# ENC28J60EthernetInterface.net
KiCad netlist of a schematic drawn in Altium Designer
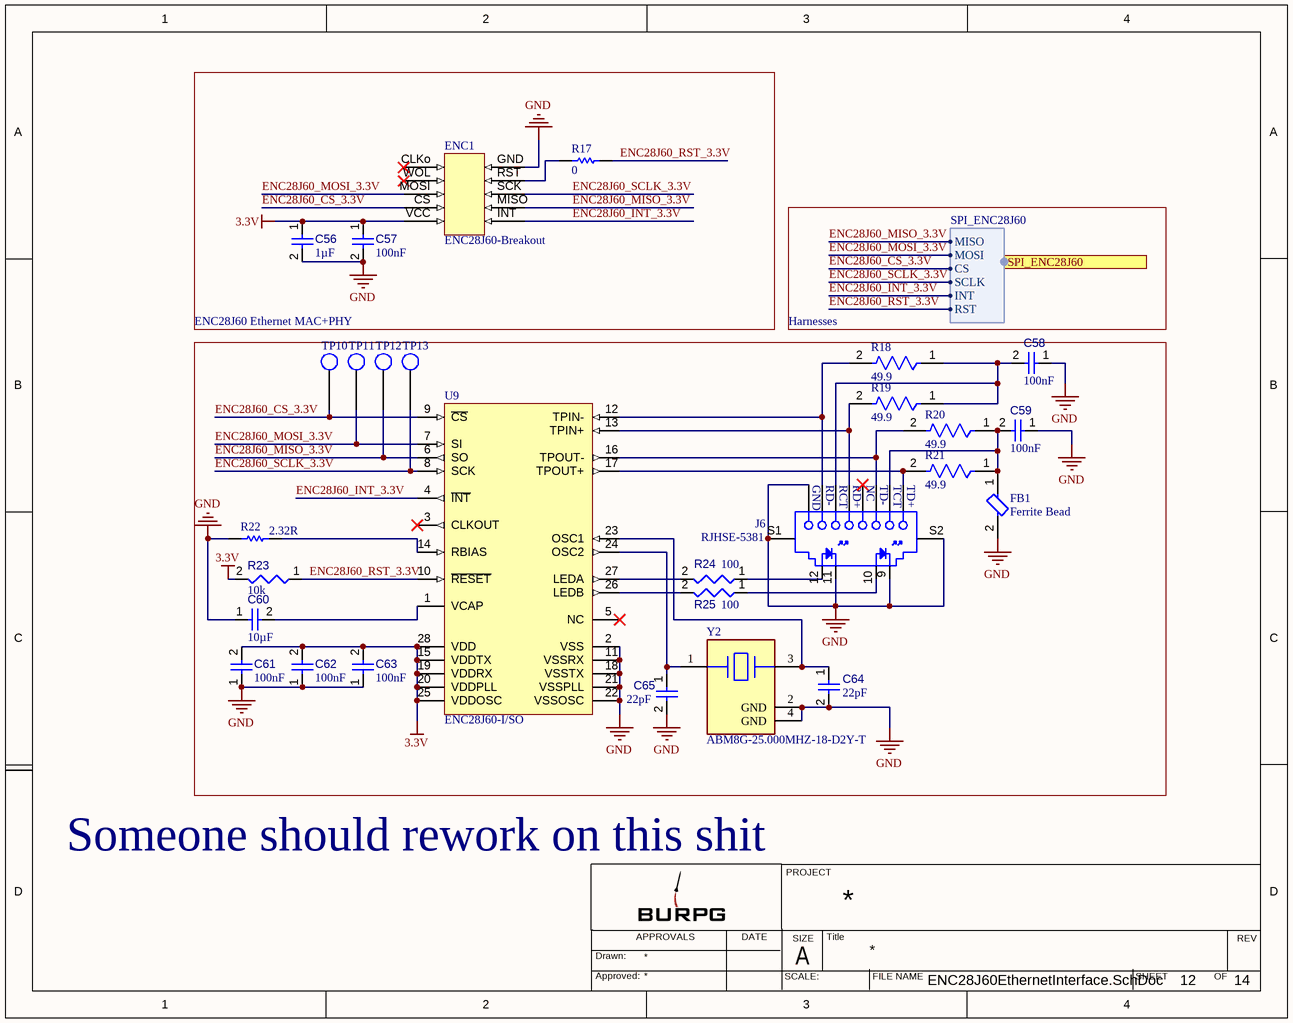
[diagram p0: ENC28J60EthernetInterface.SchDoc]

(export (version "E")
  (design (tool "Eeschema 10.0.6"))
  (components
    (comp (ref "C56")
      (value "1µF")
      (footprint "CAPC2013X135X45NL10T25")
      (description "Chip Capacitor, 1 uF, +/- 10%, 50 V, 0805 (2012 Metric)")
      (fields (field (name "TOLERANCE") "10%") (field (name "Comment") "Capacitor 1 uF +/- 10% 50 V 0805"))
      (libsource (lib "Boston University") (part "CAP-NP-2"))
    )
    (comp (ref "C57")
      (value "100nF")
      (footprint "CAPC2013X95X50LL10T25")
      (description "Chip Capacitor, 100 nF, +/- 10%, 50 V, 0805 (2012 Metric)")
      (fields (field (name "TOLERANCE") "10%") (field (name "Comment") "Capacitor 100 nF +/-10% 50 V 0805"))
      (libsource (lib "Boston University") (part "CAP-NP-2"))
    )
    (comp (ref "C58")
      (value "100nF")
      (footprint "CAPC1608X90X40NL10T20")
      (description "Chip Capacitor, 100 nF, +/- 10%, 50 V, 0603 (1608 Metric)")
      (fields (field (name "TOLERANCE") "10%") (field (name "Comment") "Capacitor 100 nF +/-10% 50 V 0603"))
      (libsource (lib "Boston University") (part "CAP-NP-2"))
    )
    (comp (ref "C59")
      (value "100nF")
      (footprint "CAPC1608X90X40NL10T20")
      (description "Chip Capacitor, 100 nF, +/- 10%, 50 V, 0603 (1608 Metric)")
      (fields (field (name "TOLERANCE") "10%") (field (name "Comment") "Capacitor 100 nF +/-10% 50 V 0603"))
      (libsource (lib "Boston University") (part "CAP-NP-2"))
    )
    (comp (ref "C60")
      (value "10µF")
      (footprint "CAPC0603(1608)100_L")
      (description "Chip Capacitor, 10µF +/-20%, 10V, 0603, Thickness 1 mm")
      (fields (field (name "TOLERANCE") "10%") (field (name "Comment") "Capacitor 10µF +/-20% 10V 0603"))
      (libsource (lib "Boston University") (part "CAP-NP-2"))
    )
    (comp (ref "C61")
      (value "100nF")
      (footprint "CAPC1608X90X40NL10T20")
      (description "Chip Capacitor, 100 nF, +/- 10%, 50 V, 0603 (1608 Metric)")
      (fields (field (name "TOLERANCE") "10%") (field (name "Comment") "Capacitor 100 nF +/-10% 50 V 0603"))
      (libsource (lib "Boston University") (part "CAP-NP-2"))
    )
    (comp (ref "C62")
      (value "100nF")
      (footprint "CAPC1608X90X40NL10T20")
      (description "Chip Capacitor, 100 nF, +/- 10%, 50 V, 0603 (1608 Metric)")
      (fields (field (name "TOLERANCE") "10%") (field (name "Comment") "Capacitor 100 nF +/-10% 50 V 0603"))
      (libsource (lib "Boston University") (part "CAP-NP-2"))
    )
    (comp (ref "C63")
      (value "100nF")
      (footprint "CAPC1608X90X40NL10T20")
      (description "Chip Capacitor, 100 nF, +/- 10%, 50 V, 0603 (1608 Metric)")
      (fields (field (name "TOLERANCE") "10%") (field (name "Comment") "Capacitor 100 nF +/-10% 50 V 0603"))
      (libsource (lib "Boston University") (part "CAP-NP-2"))
    )
    (comp (ref "C64")
      (value "22pF")
      (footprint "CAPC0402(1005)60_L")
      (description "Chip Capacitor, 22pF +/-10%, 50V, 0402, Thickness 0.6 mm")
      (fields (field (name "TOLERANCE") "10%") (field (name "Comment") "Capacitor 22pF +/-10% 50V 0402"))
      (libsource (lib "Boston University") (part "CAP-NP-2"))
    )
    (comp (ref "C65")
      (value "22pF")
      (footprint "CAPC0402(1005)60_L")
      (description "Chip Capacitor, 22pF +/-10%, 50V, 0402, Thickness 0.6 mm")
      (fields (field (name "TOLERANCE") "10%") (field (name "Comment") "Capacitor 22pF +/-10% 50V 0402"))
      (libsource (lib "Boston University") (part "CAP-NP-2"))
    )
    (comp (ref "ENC1")
      (value "ENC28J60-Breakout")
      (footprint "New footprint 1")
      (libsource (lib "Boston University") (part "New symbol 1"))
    )
    (comp (ref "FB1")
      (value "Ferrite Bead")
      (footprint "FP-MMZ1608-0_8-IPC_A")
      (description "Signal Line Ferrite Bead 60Ω  @ 100MHz 500mA DCR 150mΩ SMD 0603")
      (fields (field (name "TOLERANCE") "25%"))
      (libsource (lib "Altium Content Vault") (part "5f30dd21d616792df468990f7003faa"))
    )
    (comp (ref "J6")
      (value "RJHSE-5381")
      (footprint "AMPH-RJHSE-5381_V")
      (fields (field (name "MANUFACTURER") "Amphenol"))
      (libsource (lib "Altium Content Vault") (part "RJ45-12-2SHLD"))
    )
    (comp (ref "R17")
      (value "0")
      (footprint "RESC3216X60X45ML15T20")
      (description "Chip Resistor, 0 Ohm, +/- 5%, 0.25 W, -55 to 155 degC, 1206 (3216 Metric)")
      (fields (field (name "TOLERANCE") "5%") (field (name "POWER") "250mW"))
      (libsource (lib "Boston University") (part "RES-2"))
    )
    (comp (ref "R18")
      (value "49.9")
      (footprint "FP-ERJ6EN-MFG")
      (description "RES SMD 49.9 OHM 1% 1/8W 0805")
      (fields (field (name "TOLERANCE") "1%"))
      (libsource (lib "Altium Content Vault") (part "1029c3af85768c4190bb7ad29bc67b5"))
    )
    (comp (ref "R19")
      (value "49.9")
      (footprint "FP-ERJ6EN-MFG")
      (description "RES SMD 49.9 OHM 1% 1/8W 0805")
      (fields (field (name "TOLERANCE") "1%"))
      (libsource (lib "Altium Content Vault") (part "1029c3af85768c4190bb7ad29bc67b5"))
    )
    (comp (ref "R20")
      (value "49.9")
      (footprint "FP-ERJ6EN-MFG")
      (description "RES SMD 49.9 OHM 1% 1/8W 0805")
      (fields (field (name "TOLERANCE") "1%"))
      (libsource (lib "Altium Content Vault") (part "1029c3af85768c4190bb7ad29bc67b5"))
    )
    (comp (ref "R21")
      (value "49.9")
      (footprint "FP-ERJ6EN-MFG")
      (description "RES SMD 49.9 OHM 1% 1/8W 0805")
      (fields (field (name "TOLERANCE") "1%"))
      (libsource (lib "Altium Content Vault") (part "1029c3af85768c4190bb7ad29bc67b5"))
    )
    (comp (ref "R22")
      (value "2.32R")
      (footprint "RESC2013X70X40NL20T20")
      (fields (field (name "MANUFACTURER") "Panasonic") (field (name "PART NUMBER") "ERJ-6ENF2321V"))
      (libsource (lib "Altium Content Vault") (part "RES"))
    )
    (comp (ref "R23")
      (value "10k")
      (footprint "RESC1005X40X25ML05T05")
      (description "Chip Resistor, 10 KOhm, +/- 1%, 0.1 W, -55 to 155 degC, 0402 (1005 Metric)")
      (fields (field (name "POWER") "100mW") (field (name "TOLERANCE") "1%"))
      (libsource (lib "") (part "RES-2_1"))
    )
    (comp (ref "R24")
      (value "100")
      (footprint "RESC0402(1005)_L")
      (description "100R 0.063W 1% 0402 (1005 Metric)  SMD")
      (fields (field (name "POWER") "63mW") (field (name "TOLERANCE") "1%"))
      (libsource (lib "Boston University") (part "100R2F"))
    )
    (comp (ref "R25")
      (value "100")
      (footprint "RESC0402(1005)_L")
      (description "100R 0.063W 1% 0402 (1005 Metric)  SMD")
      (fields (field (name "POWER") "63mW") (field (name "TOLERANCE") "1%"))
      (libsource (lib "Boston University") (part "100R2F"))
    )
    (comp (ref "TP10")
      (value "BURPG_TestPoint1")
      (footprint "BURPG_TestPoint1")
      (libsource (lib "BURPG_generic") (part "BURPG_TestPoint1"))
    )
    (comp (ref "TP11")
      (value "BURPG_TestPoint1")
      (footprint "BURPG_TestPoint1")
      (libsource (lib "BURPG_generic") (part "BURPG_TestPoint1"))
    )
    (comp (ref "TP12")
      (value "BURPG_TestPoint1")
      (footprint "BURPG_TestPoint1")
      (libsource (lib "BURPG_generic") (part "BURPG_TestPoint1"))
    )
    (comp (ref "TP13")
      (value "BURPG_TestPoint1")
      (footprint "BURPG_TestPoint1")
      (libsource (lib "BURPG_generic") (part "BURPG_TestPoint1"))
    )
    (comp (ref "U9")
      (value "ENC28J60-I/SO")
      (footprint "SOIC-SO28_M")
      (description "Stand-Alone Ethernet Controller with SPI Interface, 28-Pin SOIC, Industrial Temperature")
      (libsource (lib "Altium Content Vault") (part "COM-ENET-ENC28J60-28"))
    )
    (comp (ref "Y2")
      (value "ABM8G-25.000MHZ-18-D2Y-T")
      (footprint "FP-ABM8G-MFG")
      (description "Crystal 25MHz ±20ppm (Tol) ±30ppm (Stability) 18pF FUND 60Ω 4-Pin SMD T/R")
      (fields (field (name "TOLERANCE") "20ppm"))
      (libsource (lib "Altium Content Vault") (part "48e526d86b7f2615d98721063c72f49"))
    )
  )
  (nets
    (net (code "2") (name "/ENC28J60_CS_3.3V") (class "Default")
      (node (ref "ENC1") (pin "CS") (pintype "input"))
      (node (ref "TP10") (pin "1") (pinfunction "1_1") (pintype "passive"))
      (node (ref "U9") (pin "9") (pinfunction "~{CS}_9") (pintype "input"))
    )
    (net (code "3") (name "/ENC28J60_INT_3.3V") (class "Default")
      (node (ref "ENC1") (pin "INT") (pintype "input"))
      (node (ref "U9") (pin "4") (pinfunction "~{INT}_4") (pintype "output"))
    )
    (net (code "4") (name "/ENC28J60_MISO_3.3V") (class "Default")
      (node (ref "ENC1") (pin "MISO") (pintype "input"))
      (node (ref "TP12") (pin "1") (pinfunction "1_1") (pintype "passive"))
      (node (ref "U9") (pin "6") (pinfunction "SO_6") (pintype "output"))
    )
    (net (code "5") (name "/ENC28J60_MOSI_3.3V") (class "Default")
      (node (ref "ENC1") (pin "MOSI") (pintype "input"))
      (node (ref "TP11") (pin "1") (pinfunction "1_1") (pintype "passive"))
      (node (ref "U9") (pin "7") (pinfunction "SI_7") (pintype "input"))
    )
    (net (code "6") (name "/ENC28J60_RST_3.3V") (class "Default")
      (node (ref "R17") (pin "2") (pinfunction "2_2") (pintype "passive"))
      (node (ref "R23") (pin "1") (pinfunction "1_1") (pintype "passive"))
      (node (ref "U9") (pin "10") (pinfunction "~{RESET}_10") (pintype "input"))
    )
    (net (code "7") (name "/ENC28J60_SCLK_3.3V") (class "Default")
      (node (ref "ENC1") (pin "SCK") (pintype "input"))
      (node (ref "TP13") (pin "1") (pinfunction "1_1") (pintype "passive"))
      (node (ref "U9") (pin "8") (pinfunction "SCK_8") (pintype "input"))
    )
    (net (code "9") (name "3.3V") (class "Default")
      (node (ref "C56") (pin "1") (pinfunction "1_1") (pintype "passive"))
      (node (ref "C57") (pin "1") (pinfunction "1_1") (pintype "passive"))
      (node (ref "C61") (pin "2") (pinfunction "2_2") (pintype "passive"))
      (node (ref "C62") (pin "2") (pinfunction "2_2") (pintype "passive"))
      (node (ref "C63") (pin "2") (pinfunction "2_2") (pintype "passive"))
      (node (ref "ENC1") (pin "VCC") (pintype "input"))
      (node (ref "R23") (pin "2") (pinfunction "2_2") (pintype "passive"))
      (node (ref "U9") (pin "15") (pinfunction "VDDTX_15") (pintype "power_in"))
      (node (ref "U9") (pin "19") (pinfunction "VDDRX_19") (pintype "power_in"))
      (node (ref "U9") (pin "20") (pinfunction "VDDPLL_20") (pintype "power_in"))
      (node (ref "U9") (pin "25") (pinfunction "VDDOSC_25") (pintype "power_in"))
      (node (ref "U9") (pin "28") (pinfunction "VDD_28") (pintype "power_in"))
    )
    (net (code "10") (name "GND") (class "Default")
      (node (ref "C56") (pin "2") (pinfunction "2_2") (pintype "passive"))
      (node (ref "C57") (pin "2") (pinfunction "2_2") (pintype "passive"))
      (node (ref "C58") (pin "1") (pinfunction "1_1") (pintype "passive"))
      (node (ref "C59") (pin "1") (pinfunction "1_1") (pintype "passive"))
      (node (ref "C60") (pin "1") (pinfunction "1_1") (pintype "passive"))
      (node (ref "C61") (pin "1") (pinfunction "1_1") (pintype "passive"))
      (node (ref "C62") (pin "1") (pinfunction "1_1") (pintype "passive"))
      (node (ref "C63") (pin "1") (pinfunction "1_1") (pintype "passive"))
      (node (ref "C64") (pin "2") (pinfunction "2_2") (pintype "passive"))
      (node (ref "C65") (pin "2") (pinfunction "2_2") (pintype "passive"))
      (node (ref "ENC1") (pin "GND") (pintype "input"))
      (node (ref "FB1") (pin "2") (pinfunction "2_2") (pintype "passive"))
      (node (ref "J6") (pin "11") (pinfunction "11_11") (pintype "passive"))
      (node (ref "J6") (pin "8") (pinfunction "GND_8") (pintype "passive"))
      (node (ref "J6") (pin "9") (pinfunction "9_9") (pintype "passive"))
      (node (ref "J6") (pin "S1") (pinfunction "S1_S1") (pintype "passive"))
      (node (ref "J6") (pin "S2") (pinfunction "S2_S2") (pintype "passive"))
      (node (ref "R22") (pin "1") (pinfunction "1_1") (pintype "passive"))
      (node (ref "U9") (pin "11") (pinfunction "VSSRX_11") (pintype "power_in"))
      (node (ref "U9") (pin "18") (pinfunction "VSSTX_18") (pintype "power_in"))
      (node (ref "U9") (pin "2") (pinfunction "VSS_2") (pintype "power_in"))
      (node (ref "U9") (pin "21") (pinfunction "VSSPLL_21") (pintype "power_in"))
      (node (ref "U9") (pin "22") (pinfunction "VSSOSC_22") (pintype "power_in"))
      (node (ref "Y2") (pin "2") (pinfunction "GND_2") (pintype "power_in"))
      (node (ref "Y2") (pin "4") (pinfunction "GND_4") (pintype "power_in"))
    )
    (net (code "11") (name "Net-(ENC1-PadRST)") (class "Default")
      (node (ref "ENC1") (pin "RST") (pintype "input"))
      (node (ref "R17") (pin "1") (pinfunction "1_1") (pintype "passive"))
    )
    (net (code "12") (name "Net-(J6-Pad10)") (class "Default")
      (node (ref "J6") (pin "10") (pinfunction "10_10") (pintype "passive"))
      (node (ref "R25") (pin "1") (pinfunction "1_1") (pintype "passive"))
    )
    (net (code "13") (name "Net-(J6-Pad12)") (class "Default")
      (node (ref "J6") (pin "12") (pinfunction "12_12") (pintype "passive"))
      (node (ref "R24") (pin "1") (pinfunction "1_1") (pintype "passive"))
    )
    (net (code "14") (name "Net-(J6-RCT)") (class "Default")
      (node (ref "C58") (pin "2") (pinfunction "2_2") (pintype "passive"))
      (node (ref "J6") (pin "6") (pinfunction "RCT_6") (pintype "passive"))
      (node (ref "R18") (pin "1") (pinfunction "1_1") (pintype "passive"))
      (node (ref "R19") (pin "1") (pinfunction "1_1") (pintype "passive"))
    )
    (net (code "15") (name "Net-(J6-RD+)") (class "Default")
      (node (ref "J6") (pin "5") (pinfunction "RD+_5") (pintype "passive"))
      (node (ref "R19") (pin "2") (pinfunction "2_2") (pintype "passive"))
      (node (ref "U9") (pin "13") (pinfunction "TPIN+_13") (pintype "input"))
    )
    (net (code "16") (name "Net-(J6-RD-)") (class "Default")
      (node (ref "J6") (pin "7") (pinfunction "RD-_7") (pintype "passive"))
      (node (ref "R18") (pin "2") (pinfunction "2_2") (pintype "passive"))
      (node (ref "U9") (pin "12") (pinfunction "TPIN-_12") (pintype "input"))
    )
    (net (code "17") (name "Net-(J6-TCT)") (class "Default")
      (node (ref "C59") (pin "2") (pinfunction "2_2") (pintype "passive"))
      (node (ref "FB1") (pin "1") (pinfunction "1_1") (pintype "passive"))
      (node (ref "J6") (pin "2") (pinfunction "TCT_2") (pintype "passive"))
      (node (ref "R20") (pin "1") (pinfunction "1_1") (pintype "passive"))
      (node (ref "R21") (pin "1") (pinfunction "1_1") (pintype "passive"))
    )
    (net (code "18") (name "Net-(J6-TD+)") (class "Default")
      (node (ref "J6") (pin "1") (pinfunction "TD+_1") (pintype "passive"))
      (node (ref "R21") (pin "2") (pinfunction "2_2") (pintype "passive"))
      (node (ref "U9") (pin "17") (pinfunction "TPOUT+_17") (pintype "output"))
    )
    (net (code "19") (name "Net-(J6-TD-)") (class "Default")
      (node (ref "J6") (pin "3") (pinfunction "TD-_3") (pintype "passive"))
      (node (ref "R20") (pin "2") (pinfunction "2_2") (pintype "passive"))
      (node (ref "U9") (pin "16") (pinfunction "TPOUT-_16") (pintype "output"))
    )
    (net (code "20") (name "Net-(U9-LEDA)") (class "Default")
      (node (ref "R24") (pin "2") (pinfunction "2_2") (pintype "passive"))
      (node (ref "U9") (pin "27") (pinfunction "LEDA_27") (pintype "output"))
    )
    (net (code "21") (name "Net-(U9-LEDB)") (class "Default")
      (node (ref "R25") (pin "2") (pinfunction "2_2") (pintype "passive"))
      (node (ref "U9") (pin "26") (pinfunction "LEDB_26") (pintype "output"))
    )
    (net (code "22") (name "Net-(U9-OSC1)") (class "Default")
      (node (ref "C64") (pin "1") (pinfunction "1_1") (pintype "passive"))
      (node (ref "U9") (pin "23") (pinfunction "OSC1_23") (pintype "input"))
      (node (ref "Y2") (pin "3") (pinfunction "3_3") (pintype "passive"))
    )
    (net (code "23") (name "Net-(U9-OSC2)") (class "Default")
      (node (ref "C65") (pin "1") (pinfunction "1_1") (pintype "passive"))
      (node (ref "U9") (pin "24") (pinfunction "OSC2_24") (pintype "output"))
      (node (ref "Y2") (pin "1") (pinfunction "1_1") (pintype "passive"))
    )
    (net (code "24") (name "Net-(U9-RBIAS)") (class "Default")
      (node (ref "R22") (pin "2") (pinfunction "2_2") (pintype "passive"))
      (node (ref "U9") (pin "14") (pinfunction "RBIAS_14") (pintype "input"))
    )
    (net (code "25") (name "Net-(U9-VCAP)") (class "Default")
      (node (ref "C60") (pin "2") (pinfunction "2_2") (pintype "passive"))
      (node (ref "U9") (pin "1") (pinfunction "VCAP_1") (pintype "power_in"))
    )
    (net (code "26") (name "unconnected-(ENC1-PadCLKo)") (class "Default")
      (node (ref "ENC1") (pin "CLKo") (pintype "input+no_connect"))
    )
    (net (code "27") (name "unconnected-(ENC1-PadWOL)") (class "Default")
      (node (ref "ENC1") (pin "WOL") (pintype "input+no_connect"))
    )
    (net (code "28") (name "unconnected-(J6-NC-Pad4)") (class "Default")
      (node (ref "J6") (pin "4") (pinfunction "NC_4") (pintype "passive+no_connect"))
    )
    (net (code "29") (name "unconnected-(U9-CLKOUT-Pad3)") (class "Default")
      (node (ref "U9") (pin "3") (pinfunction "CLKOUT_3") (pintype "output+no_connect"))
    )
    (net (code "30") (name "unconnected-(U9-NC-Pad5)") (class "Default")
      (node (ref "U9") (pin "5") (pinfunction "NC_5") (pintype "passive+no_connect"))
    )
  )
)
